# main.net
KiCad netlist of a schematic drawn in EAGLE
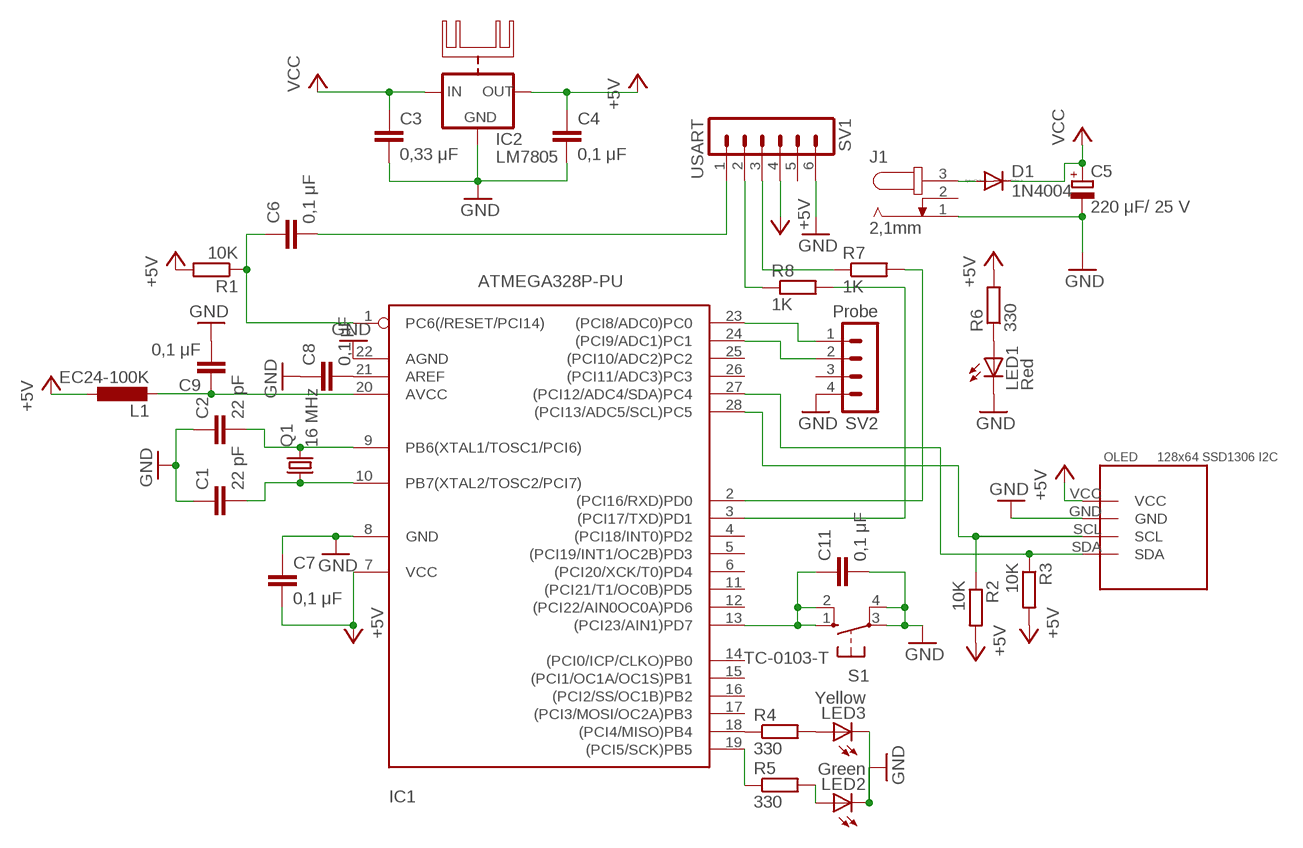
[diagram p0: schematic, sheet 1]

(export (version "E")
  (design (tool "Eeschema 10.0.6"))
  (components
    (comp (ref "C1")
      (value "22 pF")
      (footprint "eagle-import:C025-025X050")
      (libsource (lib "eagle-import") (part "C-EU025-025X050"))
    )
    (comp (ref "C2")
      (value "22 pF")
      (footprint "eagle-import:C025-025X050")
      (libsource (lib "eagle-import") (part "C-EU025-025X050"))
    )
    (comp (ref "C3")
      (value "0,33 μF")
      (footprint "eagle-import:C050-025X075")
      (libsource (lib "eagle-import") (part "C-EU050-025X075"))
    )
    (comp (ref "C4")
      (value "0,1 μF")
      (footprint "eagle-import:C050-025X075")
      (libsource (lib "eagle-import") (part "C-EU050-025X075"))
    )
    (comp (ref "C5")
      (value "220 μF/ 25 V")
      (footprint "eagle-import:E5-8,5")
      (libsource (lib "eagle-import") (part "CPOL-EUE5-8.5"))
    )
    (comp (ref "C6")
      (value "0,1 μF")
      (footprint "eagle-import:C050-025X075")
      (libsource (lib "eagle-import") (part "C-EU050-025X075"))
    )
    (comp (ref "C7")
      (value "0,1 μF")
      (footprint "eagle-import:C050-025X075")
      (libsource (lib "eagle-import") (part "C-EU050-025X075"))
    )
    (comp (ref "C8")
      (value "0,1 μF")
      (footprint "eagle-import:C050-025X075")
      (libsource (lib "eagle-import") (part "C-EU050-025X075"))
    )
    (comp (ref "C9")
      (value "0,1 μF")
      (footprint "eagle-import:C050-025X075")
      (libsource (lib "eagle-import") (part "C-EU050-025X075"))
    )
    (comp (ref "C11")
      (value "0,1 μF")
      (footprint "eagle-import:C050-025X075")
      (libsource (lib "eagle-import") (part "C-EU050-025X075"))
    )
    (comp (ref "D1")
      (value "1N4004")
      (footprint "eagle-import:DO41-10")
      (libsource (lib "eagle-import") (part "1N4004"))
    )
    (comp (ref "IC1")
      (value "ATMEGA328P-PU")
      (footprint "eagle-import:DIL28-3")
      (libsource (lib "eagle-import") (part "ATMEGA328P-20"))
    )
    (comp (ref "IC2")
      (value "LM7805")
      (footprint "eagle-import:78XXH")
      (libsource (lib "eagle-import") (part "78XXH"))
    )
    (comp (ref "J1")
      (value "2,1mm")
      (footprint "eagle-import:SPC4077")
      (libsource (lib "eagle-import") (part "JACK-PLUG0"))
    )
    (comp (ref "L1")
      (value "EC24-100K")
      (footprint "eagle-import:0207_12")
      (libsource (lib "eagle-import") (part "L-EU0207/12"))
    )
    (comp (ref "LED1")
      (value "Red")
      (footprint "eagle-import:LED5MM")
      (libsource (lib "eagle-import") (part "LED5MM"))
    )
    (comp (ref "LED2")
      (value "Green")
      (footprint "eagle-import:LED5MM")
      (libsource (lib "eagle-import") (part "LED5MM"))
    )
    (comp (ref "LED3")
      (value "Yellow")
      (footprint "eagle-import:LED5MM")
      (libsource (lib "eagle-import") (part "LED5MM"))
    )
    (comp (ref "OLED")
      (value "128x64 SSD1306 I2C")
      (footprint "eagle-import:OLED_0.96_I2C")
      (libsource (lib "eagle-import") (part "OLED_0.96_I2C"))
    )
    (comp (ref "Q1")
      (value "16 MHz")
      (footprint "eagle-import:HC49_S")
      (libsource (lib "eagle-import") (part "CRYSTALHC49S"))
    )
    (comp (ref "R1")
      (value "10K")
      (footprint "eagle-import:0207_7")
      (libsource (lib "eagle-import") (part "R-EU_0207/7"))
    )
    (comp (ref "R2")
      (value "10K")
      (footprint "eagle-import:0207_7")
      (libsource (lib "eagle-import") (part "R-EU_0207/7"))
    )
    (comp (ref "R3")
      (value "10K")
      (footprint "eagle-import:0207_7")
      (libsource (lib "eagle-import") (part "R-EU_0207/7"))
    )
    (comp (ref "R4")
      (value "330")
      (footprint "eagle-import:0207_7")
      (libsource (lib "eagle-import") (part "R-EU_0207/7"))
    )
    (comp (ref "R5")
      (value "330")
      (footprint "eagle-import:0207_7")
      (libsource (lib "eagle-import") (part "R-EU_0207/7"))
    )
    (comp (ref "R6")
      (value "330")
      (footprint "eagle-import:0207_7")
      (libsource (lib "eagle-import") (part "R-EU_0207/7"))
    )
    (comp (ref "R7")
      (value "1K")
      (footprint "eagle-import:0207_7")
      (libsource (lib "eagle-import") (part "R-EU_0207/7"))
    )
    (comp (ref "R8")
      (value "1K")
      (footprint "eagle-import:0207_7")
      (libsource (lib "eagle-import") (part "R-EU_0207/7"))
    )
    (comp (ref "S1")
      (value "TC-0103-T")
      (footprint "eagle-import:B3F-10XX")
      (fields (field (name "MPN") "B3F-1000"))
      (libsource (lib "eagle-import") (part "10-XX"))
    )
    (comp (ref "SV1")
      (value "USART")
      (footprint "eagle-import:MA06-1")
      (libsource (lib "eagle-import") (part "MA06-1"))
    )
    (comp (ref "SV2")
      (value "Probe")
      (footprint "eagle-import:MA04-1")
      (libsource (lib "eagle-import") (part "MA04-1"))
    )
  )
  (nets
    (net (code "1") (name "+5V") (class "Default")
      (node (ref "C4") (pin "1") (pinfunction "1_1") (pintype "passive"))
      (node (ref "C7") (pin "2") (pinfunction "2_2") (pintype "passive"))
      (node (ref "IC1") (pin "7") (pinfunction "VCC_7") (pintype "bidirectional"))
      (node (ref "IC2") (pin "OUT") (pinfunction "OUT_OUT") (pintype "passive"))
      (node (ref "L1") (pin "1") (pinfunction "1_1") (pintype "passive"))
      (node (ref "OLED") (pin "VCC") (pinfunction "VCC_VCC") (pintype "bidirectional"))
      (node (ref "R1") (pin "2") (pinfunction "2_2") (pintype "passive"))
      (node (ref "R2") (pin "2") (pinfunction "2_2") (pintype "passive"))
      (node (ref "R3") (pin "2") (pinfunction "2_2") (pintype "passive"))
      (node (ref "R6") (pin "2") (pinfunction "2_2") (pintype "passive"))
      (node (ref "SV1") (pin "4") (pinfunction "4_4") (pintype "passive"))
    )
    (net (code "2") (name "GND") (class "Default")
      (node (ref "C1") (pin "1") (pinfunction "1_1") (pintype "passive"))
      (node (ref "C11") (pin "2") (pinfunction "2_2") (pintype "passive"))
      (node (ref "C2") (pin "1") (pinfunction "1_1") (pintype "passive"))
      (node (ref "C3") (pin "2") (pinfunction "2_2") (pintype "passive"))
      (node (ref "C4") (pin "2") (pinfunction "2_2") (pintype "passive"))
      (node (ref "C5") (pin "-") (pinfunction "-_-") (pintype "passive"))
      (node (ref "C7") (pin "1") (pinfunction "1_1") (pintype "passive"))
      (node (ref "C8") (pin "1") (pinfunction "1_1") (pintype "passive"))
      (node (ref "C9") (pin "2") (pinfunction "2_2") (pintype "passive"))
      (node (ref "IC1") (pin "22") (pinfunction "AGND_22") (pintype "bidirectional"))
      (node (ref "IC1") (pin "8") (pinfunction "GND_8") (pintype "bidirectional"))
      (node (ref "IC2") (pin "GND") (pinfunction "GND_GND") (pintype "input"))
      (node (ref "J1") (pin "1") (pinfunction "1_1") (pintype "passive"))
      (node (ref "LED1") (pin "K") (pinfunction "C_K") (pintype "passive"))
      (node (ref "LED2") (pin "K") (pinfunction "C_K") (pintype "passive"))
      (node (ref "LED3") (pin "K") (pinfunction "C_K") (pintype "passive"))
      (node (ref "OLED") (pin "GND") (pinfunction "GND_GND") (pintype "bidirectional"))
      (node (ref "S1") (pin "3") (pinfunction "P_3") (pintype "passive"))
      (node (ref "S1") (pin "4") (pinfunction "P1_4") (pintype "passive"))
      (node (ref "SV1") (pin "6") (pinfunction "6_6") (pintype "passive"))
      (node (ref "SV2") (pin "4") (pinfunction "4_4") (pintype "passive"))
    )
    (net (code "3") (name "Net-(C6-Pad2)") (class "Default")
      (node (ref "C6") (pin "2") (pinfunction "2_2") (pintype "passive"))
      (node (ref "SV1") (pin "1") (pinfunction "1_1") (pintype "passive"))
    )
    (net (code "4") (name "Net-(D1-PadA)") (class "Default")
      (node (ref "D1") (pin "A") (pinfunction "A_A") (pintype "passive"))
      (node (ref "J1") (pin "3") (pinfunction "3_3") (pintype "passive"))
    )
    (net (code "5") (name "Net-(IC1-(PCI4{slash}MISO)PB4)") (class "Default")
      (node (ref "IC1") (pin "18") (pinfunction "(PCI4/MISO)PB4_18") (pintype "bidirectional"))
      (node (ref "R4") (pin "1") (pinfunction "1_1") (pintype "passive"))
    )
    (net (code "6") (name "Net-(IC1-(PCI5{slash}SCK)PB5)") (class "Default")
      (node (ref "IC1") (pin "19") (pinfunction "(PCI5/SCK)PB5_19") (pintype "bidirectional"))
      (node (ref "R5") (pin "1") (pinfunction "1_1") (pintype "passive"))
    )
    (net (code "7") (name "Net-(IC1-(PCI8{slash}ADC0)PC0)") (class "Default")
      (node (ref "IC1") (pin "23") (pinfunction "(PCI8/ADC0)PC0_23") (pintype "bidirectional"))
      (node (ref "SV2") (pin "1") (pinfunction "1_1") (pintype "passive"))
    )
    (net (code "8") (name "Net-(IC1-(PCI9{slash}ADC1)PC1)") (class "Default")
      (node (ref "IC1") (pin "24") (pinfunction "(PCI9/ADC1)PC1_24") (pintype "bidirectional"))
      (node (ref "SV2") (pin "2") (pinfunction "2_2") (pintype "passive"))
    )
    (net (code "9") (name "Net-(IC1-(PCI12{slash}ADC4{slash}SDA)PC4)") (class "Default")
      (node (ref "IC1") (pin "27") (pinfunction "(PCI12/ADC4/SDA)PC4_27") (pintype "bidirectional"))
      (node (ref "OLED") (pin "SDA") (pinfunction "SDA_SDA") (pintype "bidirectional"))
      (node (ref "R3") (pin "1") (pinfunction "1_1") (pintype "passive"))
    )
    (net (code "10") (name "Net-(IC1-(PCI13{slash}ADC5{slash}SCL)PC5)") (class "Default")
      (node (ref "IC1") (pin "28") (pinfunction "(PCI13/ADC5/SCL)PC5_28") (pintype "bidirectional"))
      (node (ref "OLED") (pin "SCL") (pinfunction "SCL_SCL") (pintype "bidirectional"))
      (node (ref "R2") (pin "1") (pinfunction "1_1") (pintype "passive"))
    )
    (net (code "11") (name "Net-(IC1-(PCI16{slash}RXD)PD0)") (class "Default")
      (node (ref "IC1") (pin "2") (pinfunction "(PCI16/RXD)PD0_2") (pintype "bidirectional"))
      (node (ref "R7") (pin "2") (pinfunction "2_2") (pintype "passive"))
    )
    (net (code "12") (name "Net-(IC1-(PCI17{slash}TXD)PD1)") (class "Default")
      (node (ref "IC1") (pin "3") (pinfunction "(PCI17/TXD)PD1_3") (pintype "bidirectional"))
      (node (ref "R8") (pin "2") (pinfunction "2_2") (pintype "passive"))
    )
    (net (code "13") (name "Net-(IC1-(PCI23{slash}AIN1)PD7)") (class "Default")
      (node (ref "C11") (pin "1") (pinfunction "1_1") (pintype "passive"))
      (node (ref "IC1") (pin "13") (pinfunction "(PCI23/AIN1)PD7_13") (pintype "bidirectional"))
      (node (ref "S1") (pin "1") (pinfunction "S_1") (pintype "passive"))
      (node (ref "S1") (pin "2") (pinfunction "S1_2") (pintype "passive"))
    )
    (net (code "14") (name "Net-(IC1-AREF)") (class "Default")
      (node (ref "C8") (pin "2") (pinfunction "2_2") (pintype "passive"))
      (node (ref "IC1") (pin "21") (pinfunction "AREF_21") (pintype "bidirectional"))
    )
    (net (code "15") (name "Net-(IC1-AVCC)") (class "Default")
      (node (ref "C9") (pin "1") (pinfunction "1_1") (pintype "passive"))
      (node (ref "IC1") (pin "20") (pinfunction "AVCC_20") (pintype "bidirectional"))
      (node (ref "L1") (pin "2") (pinfunction "2_2") (pintype "passive"))
    )
    (net (code "16") (name "Net-(IC1-PB6(XTAL1{slash}TOSC1{slash}PCI6))") (class "Default")
      (node (ref "C2") (pin "2") (pinfunction "2_2") (pintype "passive"))
      (node (ref "IC1") (pin "9") (pinfunction "PB6(XTAL1/TOSC1/PCI6)_9") (pintype "bidirectional"))
      (node (ref "Q1") (pin "2") (pinfunction "2_2") (pintype "passive"))
    )
    (net (code "17") (name "Net-(IC1-PB7(XTAL2{slash}TOSC2{slash}PCI7))") (class "Default")
      (node (ref "C1") (pin "2") (pinfunction "2_2") (pintype "passive"))
      (node (ref "IC1") (pin "10") (pinfunction "PB7(XTAL2/TOSC2/PCI7)_10") (pintype "bidirectional"))
      (node (ref "Q1") (pin "1") (pinfunction "1_1") (pintype "passive"))
    )
    (net (code "18") (name "Net-(IC1-PC6({slash}RESET{slash}PCI14))") (class "Default")
      (node (ref "C6") (pin "1") (pinfunction "1_1") (pintype "passive"))
      (node (ref "IC1") (pin "1") (pinfunction "PC6(/RESET/PCI14)_1") (pintype "bidirectional"))
      (node (ref "R1") (pin "1") (pinfunction "1_1") (pintype "passive"))
    )
    (net (code "19") (name "Net-(LED1-PadA)") (class "Default")
      (node (ref "LED1") (pin "A") (pinfunction "A_A") (pintype "passive"))
      (node (ref "R6") (pin "1") (pinfunction "1_1") (pintype "passive"))
    )
    (net (code "20") (name "Net-(LED2-PadA)") (class "Default")
      (node (ref "LED2") (pin "A") (pinfunction "A_A") (pintype "passive"))
      (node (ref "R5") (pin "2") (pinfunction "2_2") (pintype "passive"))
    )
    (net (code "21") (name "Net-(LED3-PadA)") (class "Default")
      (node (ref "LED3") (pin "A") (pinfunction "A_A") (pintype "passive"))
      (node (ref "R4") (pin "2") (pinfunction "2_2") (pintype "passive"))
    )
    (net (code "22") (name "Net-(R7-Pad1)") (class "Default")
      (node (ref "R7") (pin "1") (pinfunction "1_1") (pintype "passive"))
      (node (ref "SV1") (pin "3") (pinfunction "3_3") (pintype "passive"))
    )
    (net (code "23") (name "Net-(R8-Pad1)") (class "Default")
      (node (ref "R8") (pin "1") (pinfunction "1_1") (pintype "passive"))
      (node (ref "SV1") (pin "2") (pinfunction "2_2") (pintype "passive"))
    )
    (net (code "24") (name "VCC") (class "Default")
      (node (ref "C3") (pin "1") (pinfunction "1_1") (pintype "passive"))
      (node (ref "C5") (pin "+") (pinfunction "+_+") (pintype "passive"))
      (node (ref "D1") (pin "C") (pinfunction "C_C") (pintype "passive"))
      (node (ref "IC2") (pin "IN") (pinfunction "IN_IN") (pintype "input"))
    )
    (net (code "25") (name "unconnected-(IC1-(PCI0{slash}ICP{slash}CLKO)PB0-Pad14)") (class "Default")
      (node (ref "IC1") (pin "14") (pinfunction "(PCI0/ICP/CLKO)PB0_14") (pintype "bidirectional"))
    )
    (net (code "26") (name "unconnected-(IC1-(PCI1{slash}OC1A{slash}OC1S)PB1-Pad15)") (class "Default")
      (node (ref "IC1") (pin "15") (pinfunction "(PCI1/OC1A/OC1S)PB1_15") (pintype "bidirectional"))
    )
    (net (code "27") (name "unconnected-(IC1-(PCI2{slash}SS{slash}OC1B)PB2-Pad16)") (class "Default")
      (node (ref "IC1") (pin "16") (pinfunction "(PCI2/SS/OC1B)PB2_16") (pintype "bidirectional"))
    )
    (net (code "28") (name "unconnected-(IC1-(PCI3{slash}MOSI{slash}OC2A)PB3-Pad17)") (class "Default")
      (node (ref "IC1") (pin "17") (pinfunction "(PCI3/MOSI/OC2A)PB3_17") (pintype "bidirectional"))
    )
    (net (code "29") (name "unconnected-(IC1-(PCI10{slash}ADC2)PC2-Pad25)") (class "Default")
      (node (ref "IC1") (pin "25") (pinfunction "(PCI10/ADC2)PC2_25") (pintype "bidirectional"))
    )
    (net (code "30") (name "unconnected-(IC1-(PCI11{slash}ADC3)PC3-Pad26)") (class "Default")
      (node (ref "IC1") (pin "26") (pinfunction "(PCI11/ADC3)PC3_26") (pintype "bidirectional"))
    )
    (net (code "31") (name "unconnected-(IC1-(PCI18{slash}INT0)PD2-Pad4)") (class "Default")
      (node (ref "IC1") (pin "4") (pinfunction "(PCI18/INT0)PD2_4") (pintype "bidirectional"))
    )
    (net (code "32") (name "unconnected-(IC1-(PCI19{slash}INT1{slash}OC2B)PD3-Pad5)") (class "Default")
      (node (ref "IC1") (pin "5") (pinfunction "(PCI19/INT1/OC2B)PD3_5") (pintype "bidirectional"))
    )
    (net (code "33") (name "unconnected-(IC1-(PCI20{slash}XCK{slash}T0)PD4-Pad6)") (class "Default")
      (node (ref "IC1") (pin "6") (pinfunction "(PCI20/XCK/T0)PD4_6") (pintype "bidirectional"))
    )
    (net (code "34") (name "unconnected-(IC1-(PCI21{slash}T1{slash}OC0B)PD5-Pad11)") (class "Default")
      (node (ref "IC1") (pin "11") (pinfunction "(PCI21/T1/OC0B)PD5_11") (pintype "bidirectional"))
    )
    (net (code "35") (name "unconnected-(IC1-(PCI22{slash}AIN0OC0A)PD6-Pad12)") (class "Default")
      (node (ref "IC1") (pin "12") (pinfunction "(PCI22/AIN0OC0A)PD6_12") (pintype "bidirectional"))
    )
    (net (code "36") (name "unconnected-(J1-Pad2)") (class "Default")
      (node (ref "J1") (pin "2") (pinfunction "2_2") (pintype "passive"))
    )
    (net (code "37") (name "unconnected-(SV1-Pad5)") (class "Default")
      (node (ref "SV1") (pin "5") (pinfunction "5_5") (pintype "passive"))
    )
    (net (code "38") (name "unconnected-(SV2-Pad3)") (class "Default")
      (node (ref "SV2") (pin "3") (pinfunction "3_3") (pintype "passive"))
    )
  )
)
